# ui_lcd.net
KiCad netlist of a schematic drawn in Altium Designer
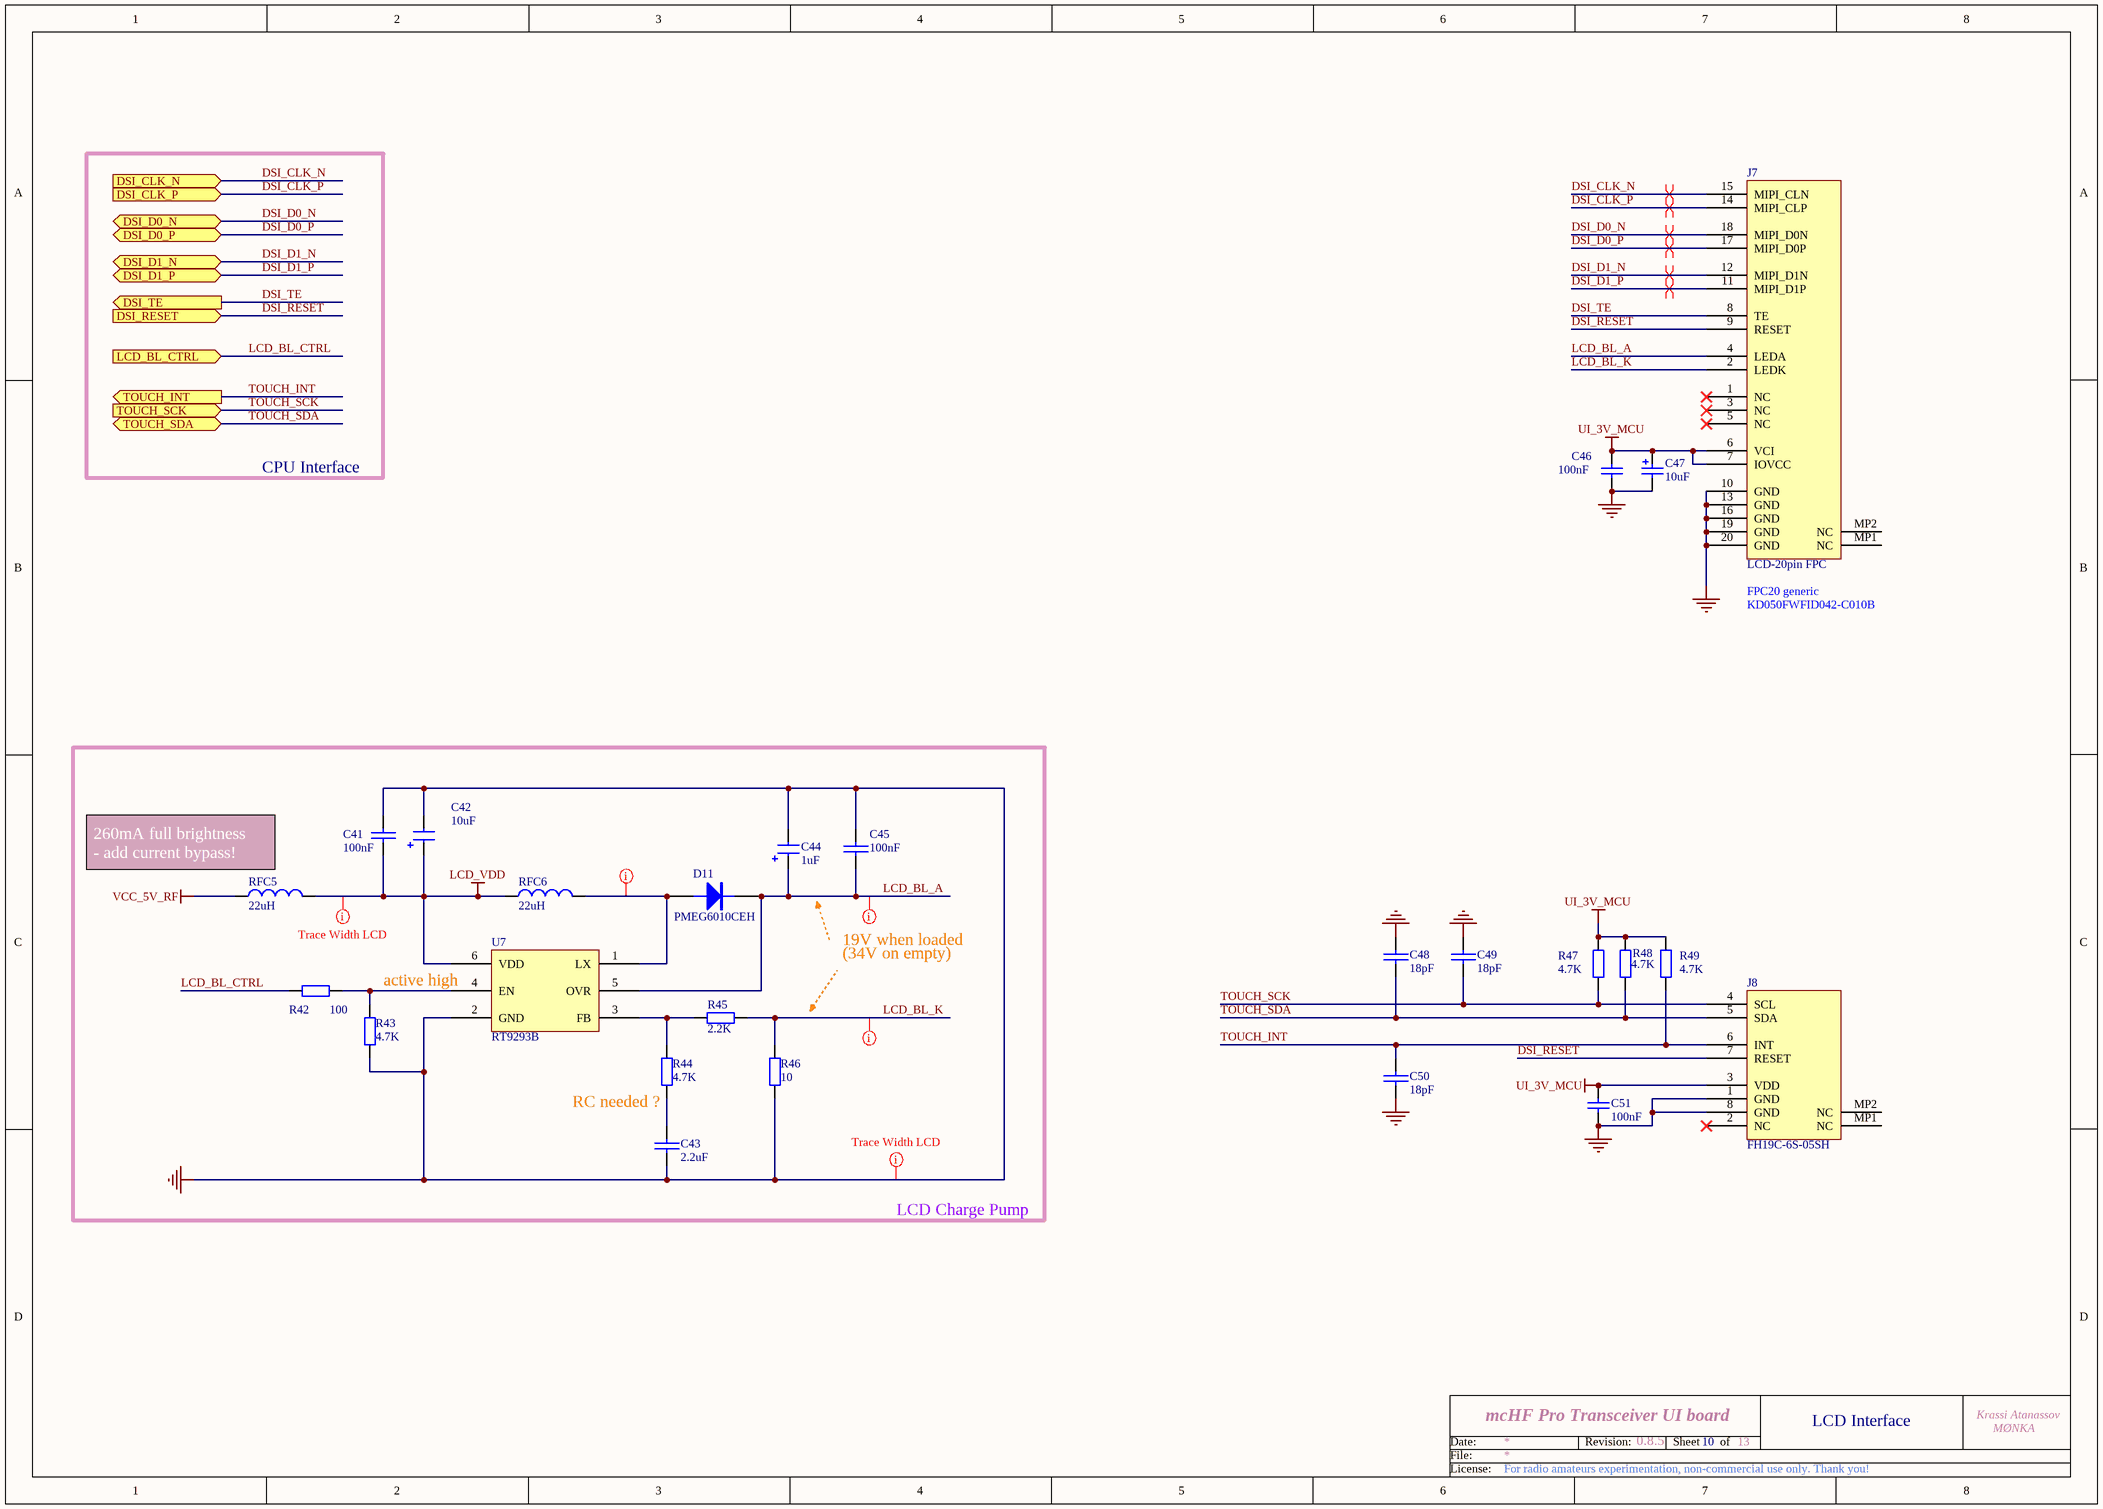
[diagram p0: ui_lcd.SchDoc]

(export (version "E")
  (design (tool "Eeschema 10.0.6"))
  (components
    (comp (ref "C41")
      (value "100nF")
      (footprint "0805")
      (description "Capacitor")
      (libsource (lib "mcHF_ui") (part "CAP"))
    )
    (comp (ref "C42")
      (value "10uF")
      (footprint "1206_Elec_Cap")
      (description "Electrolitic capacitor")
      (libsource (lib "mcHF_ui") (part "CAP-POL"))
    )
    (comp (ref "C43")
      (value "2.2uF")
      (footprint "0805")
      (description "Ceramic Capacitor")
      (libsource (lib "mcHF_ui") (part "CAP"))
    )
    (comp (ref "C44")
      (value "1uF")
      (footprint "1206_Elec_Cap")
      (description "Electrolitic capacitor")
      (fields (field (name "VOLTAGE") "50V"))
      (libsource (lib "mcHF_ui") (part "CAP-POL"))
    )
    (comp (ref "C45")
      (value "100nF")
      (footprint "0805")
      (description "Capacitor")
      (libsource (lib "mcHF_ui") (part "CAP"))
    )
    (comp (ref "C46")
      (value "100nF")
      (footprint "0805")
      (description "Capacitor")
      (fields (field (name "PUBLISHER") "Altium Limited"))
      (libsource (lib "Miscellaneous Devices") (part "CAP"))
    )
    (comp (ref "C47")
      (value "10uF")
      (footprint "1206_Elec_Cap")
      (fields (field (name "PUBLISHER") "Altium Limited"))
      (libsource (lib "Miscellaneous Devices") (part "Cap Pol1"))
    )
    (comp (ref "C48")
      (value "18pF")
      (footprint "0805")
      (description "Capacitor")
      (fields (field (name "VOLTAGE") "100V"))
      (libsource (lib "mcHF_rf") (part "CAP"))
    )
    (comp (ref "C49")
      (value "18pF")
      (footprint "0805")
      (description "Capacitor")
      (fields (field (name "VOLTAGE") "100V"))
      (libsource (lib "mcHF_rf") (part "CAP"))
    )
    (comp (ref "C50")
      (value "18pF")
      (footprint "0805")
      (description "Capacitor")
      (fields (field (name "VOLTAGE") "100V"))
      (libsource (lib "mcHF_rf") (part "CAP"))
    )
    (comp (ref "C51")
      (value "100nF")
      (footprint "0805")
      (description "Capacitor")
      (fields (field (name "PUBLISHER") "Altium Limited"))
      (libsource (lib "Miscellaneous Devices") (part "CAP"))
    )
    (comp (ref "D11")
      (value "PMEG6010CEH")
      (footprint "SOD87")
      (description "DIODE, SCHOTTKY, 1A, 60V, SOD-123F")
      (libsource (lib "mcHF_rf") (part "PMEG6010CEH"))
    )
    (comp (ref "J7")
      (value "LCD-20pin FPC")
      (footprint "MOLX-52746-2071")
      (description "LCD-20pin FPC, Top contacts position")
      (libsource (lib "__ui") (part "KD050FWFID042-C010B"))
    )
    (comp (ref "J8")
      (value "FH19C-6S-05SH")
      (footprint "MOLX-501461-0891")
      (description "8 pin FPC, Top contacts position")
      (libsource (lib "__ui") (part "FPC8"))
    )
    (comp (ref "R42")
      (value "100")
      (footprint "0805")
      (description "Resistor")
      (libsource (lib "mcHF_rf") (part "RES"))
    )
    (comp (ref "R43")
      (value "4.7K")
      (footprint "0805")
      (description "Resistor")
      (libsource (lib "mcHF_ui") (part "RES"))
    )
    (comp (ref "R44")
      (value "4.7K")
      (footprint "0805")
      (description "Resistor")
      (libsource (lib "mcHF_ui") (part "RES"))
    )
    (comp (ref "R45")
      (value "2.2K")
      (footprint "0805")
      (description "Resistor")
      (libsource (lib "") (part "RES_1"))
    )
    (comp (ref "R46")
      (value "10")
      (footprint "1206")
      (description "Resistor")
      (libsource (lib "mcHF_ui") (part "RES"))
    )
    (comp (ref "R47")
      (value "4.7K")
      (footprint "0805")
      (description "Resistor")
      (libsource (lib "*") (part "RES"))
    )
    (comp (ref "R48")
      (value "4.7K")
      (footprint "0805")
      (description "Resistor")
      (libsource (lib "*") (part "RES"))
    )
    (comp (ref "R49")
      (value "4.7K")
      (footprint "0805")
      (description "Resistor")
      (libsource (lib "*") (part "RES"))
    )
    (comp (ref "RFC5")
      (value "22uH")
      (footprint "0805")
      (description "Power Inductor")
      (libsource (lib "mcHF_ui") (part "Inductor"))
    )
    (comp (ref "RFC6")
      (value "22uH")
      (footprint "0805")
      (description "Power Inductor")
      (libsource (lib "mcHF_ui") (part "Inductor"))
    )
    (comp (ref "U7")
      (value "RT9293B")
      (footprint "SOT25-6")
      (description "Charge Pump")
      (libsource (lib "mcHF_ui_b") (part "RT9293B"))
    )
  )
  (nets
    (net (code "1") (name "/DSI_CLK_N") (class "Default")
      (node (ref "J7") (pin "15") (pinfunction "MIPI_CLN_15") (pintype "passive"))
    )
    (net (code "2") (name "/DSI_CLK_P") (class "Default")
      (node (ref "J7") (pin "14") (pinfunction "MIPI_CLP_14") (pintype "passive"))
    )
    (net (code "3") (name "/DSI_D0_N") (class "Default")
      (node (ref "J7") (pin "18") (pinfunction "MIPI_D0N_18") (pintype "passive"))
    )
    (net (code "4") (name "/DSI_D0_P") (class "Default")
      (node (ref "J7") (pin "17") (pinfunction "MIPI_D0P_17") (pintype "passive"))
    )
    (net (code "5") (name "/DSI_D1_N") (class "Default")
      (node (ref "J7") (pin "12") (pinfunction "MIPI_D1N_12") (pintype "passive"))
    )
    (net (code "6") (name "/DSI_D1_P") (class "Default")
      (node (ref "J7") (pin "11") (pinfunction "MIPI_D1P_11") (pintype "passive"))
    )
    (net (code "7") (name "/DSI_RESET") (class "Default")
      (node (ref "J7") (pin "9") (pinfunction "RESET_9") (pintype "passive"))
      (node (ref "J8") (pin "7") (pinfunction "RESET_7") (pintype "passive"))
    )
    (net (code "8") (name "/DSI_TE") (class "Default")
      (node (ref "J7") (pin "8") (pinfunction "TE_8") (pintype "passive"))
    )
    (net (code "9") (name "/LCD_BL_A") (class "Default")
      (node (ref "C44") (pin "1") (pinfunction "1_1") (pintype "passive"))
      (node (ref "C45") (pin "2") (pinfunction "2_2") (pintype "passive"))
      (node (ref "D11") (pin "2") (pinfunction "K_2") (pintype "passive"))
      (node (ref "J7") (pin "4") (pinfunction "LEDA_4") (pintype "passive"))
      (node (ref "U7") (pin "5") (pinfunction "OVR_5") (pintype "passive"))
    )
    (net (code "10") (name "/LCD_BL_CTRL") (class "Default")
      (node (ref "R42") (pin "1") (pinfunction "1_1") (pintype "passive"))
    )
    (net (code "11") (name "/LCD_BL_K") (class "Default")
      (node (ref "J7") (pin "2") (pinfunction "LEDK_2") (pintype "passive"))
      (node (ref "R45") (pin "2") (pinfunction "2_2") (pintype "passive"))
      (node (ref "R46") (pin "2") (pinfunction "2_2") (pintype "passive"))
    )
    (net (code "12") (name "/TOUCH_INT") (class "Default")
      (node (ref "C50") (pin "1") (pinfunction "1_1") (pintype "passive"))
      (node (ref "J8") (pin "6") (pinfunction "INT_6") (pintype "passive"))
      (node (ref "R49") (pin "2") (pinfunction "2_2") (pintype "passive"))
    )
    (net (code "13") (name "/TOUCH_SCK") (class "Default")
      (node (ref "C49") (pin "2") (pinfunction "2_2") (pintype "passive"))
      (node (ref "J8") (pin "4") (pinfunction "SCL_4") (pintype "passive"))
      (node (ref "R47") (pin "2") (pinfunction "2_2") (pintype "passive"))
    )
    (net (code "14") (name "/TOUCH_SDA") (class "Default")
      (node (ref "C48") (pin "2") (pinfunction "2_2") (pintype "passive"))
      (node (ref "J8") (pin "5") (pinfunction "SDA_5") (pintype "passive"))
      (node (ref "R48") (pin "2") (pinfunction "2_2") (pintype "passive"))
    )
    (net (code "15") (name "GND") (class "Default")
      (node (ref "C41") (pin "1") (pinfunction "1_1") (pintype "passive"))
      (node (ref "C42") (pin "2") (pinfunction "2_2") (pintype "passive"))
      (node (ref "C43") (pin "2") (pinfunction "2_2") (pintype "passive"))
      (node (ref "C44") (pin "2") (pinfunction "2_2") (pintype "passive"))
      (node (ref "C45") (pin "1") (pinfunction "1_1") (pintype "passive"))
      (node (ref "C46") (pin "1") (pinfunction "1_1") (pintype "passive"))
      (node (ref "C47") (pin "2") (pinfunction "2_2") (pintype "passive"))
      (node (ref "C48") (pin "1") (pinfunction "1_1") (pintype "passive"))
      (node (ref "C49") (pin "1") (pinfunction "1_1") (pintype "passive"))
      (node (ref "C50") (pin "2") (pinfunction "2_2") (pintype "passive"))
      (node (ref "C51") (pin "1") (pinfunction "1_1") (pintype "passive"))
      (node (ref "J7") (pin "10") (pinfunction "GND_10") (pintype "passive"))
      (node (ref "J7") (pin "13") (pinfunction "GND_13") (pintype "passive"))
      (node (ref "J7") (pin "16") (pinfunction "GND_16") (pintype "passive"))
      (node (ref "J7") (pin "19") (pinfunction "GND_19") (pintype "passive"))
      (node (ref "J7") (pin "20") (pinfunction "GND_20") (pintype "passive"))
      (node (ref "J8") (pin "1") (pinfunction "GND_1") (pintype "passive"))
      (node (ref "J8") (pin "8") (pinfunction "GND_8") (pintype "passive"))
      (node (ref "R43") (pin "1") (pinfunction "1_1") (pintype "passive"))
      (node (ref "R46") (pin "1") (pinfunction "1_1") (pintype "passive"))
      (node (ref "U7") (pin "2") (pinfunction "GND_2") (pintype "passive"))
    )
    (net (code "16") (name "LCD_VDD") (class "Default")
      (node (ref "C41") (pin "2") (pinfunction "2_2") (pintype "passive"))
      (node (ref "C42") (pin "1") (pinfunction "1_1") (pintype "passive"))
      (node (ref "RFC5") (pin "2") (pinfunction "2_2") (pintype "passive"))
      (node (ref "RFC6") (pin "1") (pinfunction "1_1") (pintype "passive"))
      (node (ref "U7") (pin "6") (pinfunction "VDD_6") (pintype "passive"))
    )
    (net (code "17") (name "Net-(C43-Pad1)") (class "Default")
      (node (ref "C43") (pin "1") (pinfunction "1_1") (pintype "passive"))
      (node (ref "R44") (pin "1") (pinfunction "1_1") (pintype "passive"))
    )
    (net (code "18") (name "Net-(D11-A)") (class "Default")
      (node (ref "D11") (pin "1") (pinfunction "A_1") (pintype "passive"))
      (node (ref "RFC6") (pin "2") (pinfunction "2_2") (pintype "passive"))
      (node (ref "U7") (pin "1") (pinfunction "LX_1") (pintype "passive"))
    )
    (net (code "19") (name "Net-(U7-EN)") (class "Default")
      (node (ref "R42") (pin "2") (pinfunction "2_2") (pintype "passive"))
      (node (ref "R43") (pin "2") (pinfunction "2_2") (pintype "passive"))
      (node (ref "U7") (pin "4") (pinfunction "EN_4") (pintype "passive"))
    )
    (net (code "20") (name "Net-(U7-FB)") (class "Default")
      (node (ref "R44") (pin "2") (pinfunction "2_2") (pintype "passive"))
      (node (ref "R45") (pin "1") (pinfunction "1_1") (pintype "passive"))
      (node (ref "U7") (pin "3") (pinfunction "FB_3") (pintype "passive"))
    )
    (net (code "21") (name "UI_3V_MCU") (class "Default")
      (node (ref "C46") (pin "2") (pinfunction "2_2") (pintype "passive"))
      (node (ref "C47") (pin "1") (pinfunction "1_1") (pintype "passive"))
      (node (ref "C51") (pin "2") (pinfunction "2_2") (pintype "passive"))
      (node (ref "J7") (pin "6") (pinfunction "VCI_6") (pintype "passive"))
      (node (ref "J7") (pin "7") (pinfunction "IOVCC_7") (pintype "passive"))
      (node (ref "J8") (pin "3") (pinfunction "VDD_3") (pintype "passive"))
      (node (ref "R47") (pin "1") (pinfunction "1_1") (pintype "passive"))
      (node (ref "R48") (pin "1") (pinfunction "1_1") (pintype "passive"))
      (node (ref "R49") (pin "1") (pinfunction "1_1") (pintype "passive"))
    )
    (net (code "22") (name "VCC_5V_RF") (class "Default")
      (node (ref "RFC5") (pin "1") (pinfunction "1_1") (pintype "passive"))
    )
    (net (code "23") (name "unconnected-(J7-NC-Pad1)") (class "Default")
      (node (ref "J7") (pin "1") (pinfunction "NC_1") (pintype "passive+no_connect"))
    )
    (net (code "24") (name "unconnected-(J7-NC-Pad3)") (class "Default")
      (node (ref "J7") (pin "3") (pinfunction "NC_3") (pintype "passive+no_connect"))
    )
    (net (code "25") (name "unconnected-(J7-NC-Pad5)") (class "Default")
      (node (ref "J7") (pin "5") (pinfunction "NC_5") (pintype "passive+no_connect"))
    )
    (net (code "26") (name "unconnected-(J7-NC-PadMP1)") (class "Default")
      (node (ref "J7") (pin "MP1") (pinfunction "NC_MP1") (pintype "passive"))
    )
    (net (code "27") (name "unconnected-(J7-NC-PadMP2)") (class "Default")
      (node (ref "J7") (pin "MP2") (pinfunction "NC_MP2") (pintype "passive"))
    )
    (net (code "28") (name "unconnected-(J8-NC-Pad2)") (class "Default")
      (node (ref "J8") (pin "2") (pinfunction "NC_2") (pintype "passive+no_connect"))
    )
    (net (code "29") (name "unconnected-(J8-NC-PadMP1)") (class "Default")
      (node (ref "J8") (pin "MP1") (pinfunction "NC_MP1") (pintype "passive"))
    )
    (net (code "30") (name "unconnected-(J8-NC-PadMP2)") (class "Default")
      (node (ref "J8") (pin "MP2") (pinfunction "NC_MP2") (pintype "passive"))
    )
  )
)
